# AD9854_V2_1.net
KiCad netlist of a schematic drawn in Altium Designer
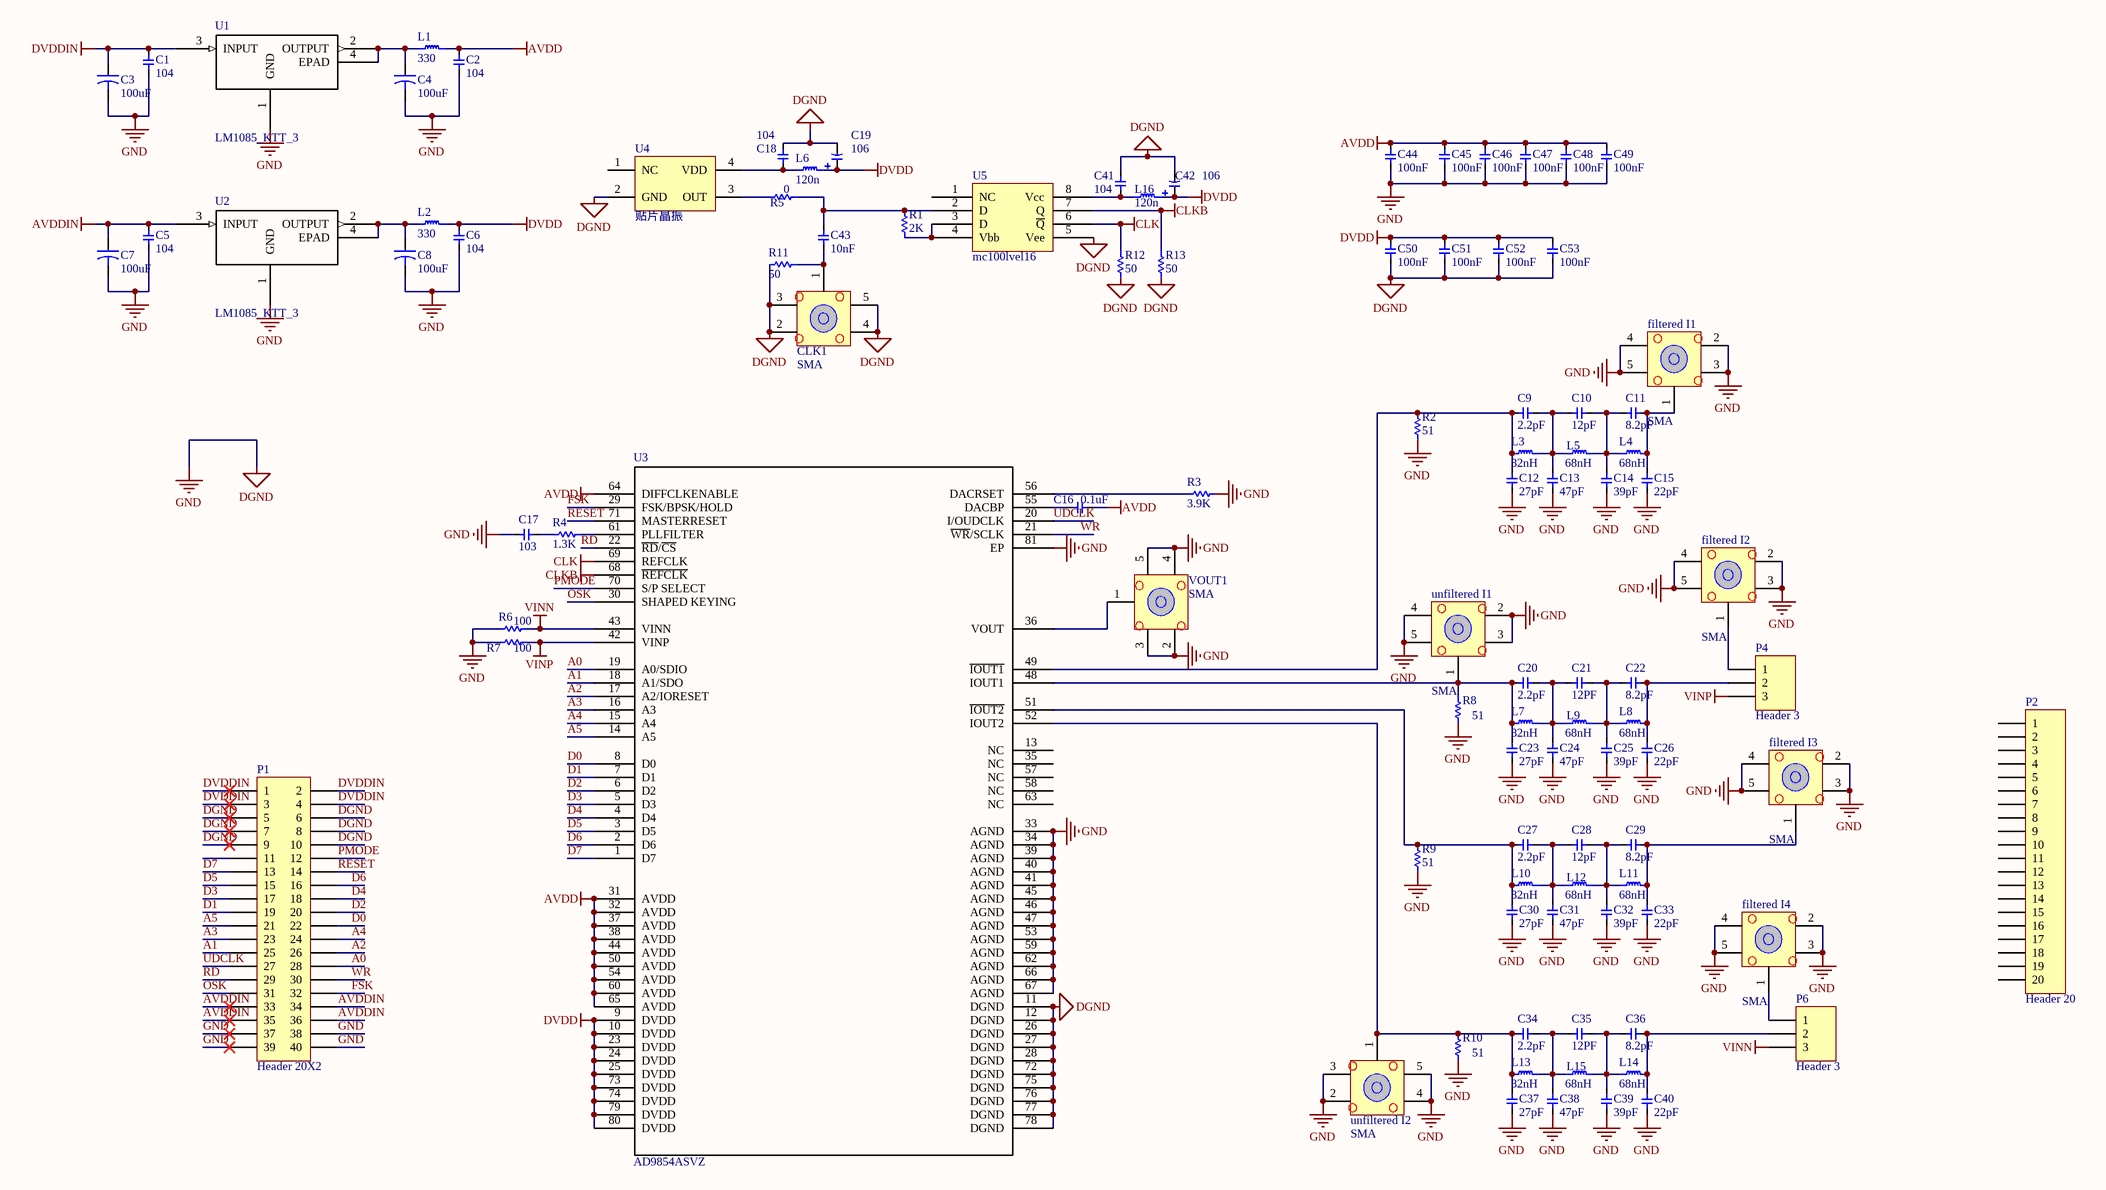
[diagram p0: AD9854_V2.1.SchDoc]

(export (version "E")
  (design (tool "Eeschema 10.0.6"))
  (components
    (comp (ref "C1")
      (value "104")
      (footprint "0805")
      (description "Capacitor")
      (fields (field (name "Comment") "Cap") (field (name "PUBLISHER") "Altium Limited"))
      (libsource (lib "Basic devices") (part "Cap"))
    )
    (comp (ref "C2")
      (value "104")
      (footprint "0805")
      (description "Capacitor")
      (fields (field (name "Comment") "Cap") (field (name "PUBLISHER") "Altium Limited"))
      (libsource (lib "Basic devices") (part "Cap"))
    )
    (comp (ref "C3")
      (value "100uF")
      (footprint "CAPR5-4X5")
      (description "Capacitor")
      (fields (field (name "Comment") "Cap2") (field (name "PUBLISHER") "Altium Limited"))
      (libsource (lib "Miscellaneous Devices") (part "Cap2"))
    )
    (comp (ref "C4")
      (value "100uF")
      (footprint "CAPR5-4X5")
      (description "Capacitor")
      (fields (field (name "Comment") "Cap2") (field (name "PUBLISHER") "Altium Limited"))
      (libsource (lib "Miscellaneous Devices") (part "Cap2"))
    )
    (comp (ref "C5")
      (value "104")
      (footprint "0805")
      (description "Capacitor")
      (fields (field (name "Comment") "Cap") (field (name "PUBLISHER") "Altium Limited"))
      (libsource (lib "Basic devices") (part "Cap"))
    )
    (comp (ref "C6")
      (value "104")
      (footprint "0805")
      (description "Capacitor")
      (fields (field (name "Comment") "Cap") (field (name "PUBLISHER") "Altium Limited"))
      (libsource (lib "Basic devices") (part "Cap"))
    )
    (comp (ref "C7")
      (value "100uF")
      (footprint "CAPR5-4X5")
      (description "Capacitor")
      (fields (field (name "Comment") "Cap2") (field (name "PUBLISHER") "Altium Limited"))
      (libsource (lib "Miscellaneous Devices") (part "Cap2"))
    )
    (comp (ref "C8")
      (value "100uF")
      (footprint "CAPR5-4X5")
      (description "Capacitor")
      (fields (field (name "Comment") "Cap2") (field (name "PUBLISHER") "Altium Limited"))
      (libsource (lib "Miscellaneous Devices") (part "Cap2"))
    )
    (comp (ref "C9")
      (value "2.2pF")
      (footprint "0805")
      (description "Capacitor")
      (fields (field (name "Comment") "Cap") (field (name "PUBLISHER") "Altium Limited"))
      (libsource (lib "Basic devices") (part "Cap"))
    )
    (comp (ref "C10")
      (value "12pF")
      (footprint "0805")
      (description "Capacitor")
      (fields (field (name "Comment") "Cap") (field (name "PUBLISHER") "Altium Limited"))
      (libsource (lib "Basic devices") (part "Cap"))
    )
    (comp (ref "C11")
      (value "8.2pF")
      (footprint "0805")
      (description "Capacitor")
      (fields (field (name "Comment") "Cap") (field (name "PUBLISHER") "Altium Limited"))
      (libsource (lib "Basic devices") (part "Cap"))
    )
    (comp (ref "C12")
      (value "27pF")
      (footprint "0805")
      (description "Capacitor")
      (fields (field (name "Comment") "Cap") (field (name "PUBLISHER") "Altium Limited"))
      (libsource (lib "Basic devices") (part "Cap"))
    )
    (comp (ref "C13")
      (value "47pF")
      (footprint "0805")
      (description "Capacitor")
      (fields (field (name "Comment") "Cap") (field (name "PUBLISHER") "Altium Limited"))
      (libsource (lib "Basic devices") (part "Cap"))
    )
    (comp (ref "C14")
      (value "39pF")
      (footprint "0805")
      (description "Capacitor")
      (fields (field (name "Comment") "Cap") (field (name "PUBLISHER") "Altium Limited"))
      (libsource (lib "Basic devices") (part "Cap"))
    )
    (comp (ref "C15")
      (value "22pF")
      (footprint "0805")
      (description "Capacitor")
      (fields (field (name "Comment") "Cap") (field (name "PUBLISHER") "Altium Limited"))
      (libsource (lib "Basic devices") (part "Cap"))
    )
    (comp (ref "C16")
      (value "0.1uF")
      (footprint "0805")
      (description "Capacitor")
      (fields (field (name "Comment") "Cap") (field (name "PUBLISHER") "Altium Limited"))
      (libsource (lib "Basic devices") (part "Cap"))
    )
    (comp (ref "C17")
      (value "103")
      (footprint "0805")
      (description "Capacitor")
      (fields (field (name "Comment") "Cap") (field (name "PUBLISHER") "Altium Limited"))
      (libsource (lib "Basic devices") (part "Cap"))
    )
    (comp (ref "C18")
      (value "104")
      (footprint "0805")
      (description "Capacitor")
      (fields (field (name "Comment") "Cap") (field (name "PUBLISHER") "Altium Limited"))
      (libsource (lib "Basic devices") (part "Cap"))
    )
    (comp (ref "C19")
      (value "106")
      (footprint "c1206 - duplicate")
      (description "Polarized Capacitor (Axial)")
      (fields (field (name "Comment") "Cap Pol") (field (name "PUBLISHER") "Altium Limited"))
      (libsource (lib "Basic devices") (part "Cap Pol"))
    )
    (comp (ref "C20")
      (value "2.2pF")
      (footprint "0805")
      (description "Capacitor")
      (fields (field (name "Comment") "Cap") (field (name "PUBLISHER") "Altium Limited"))
      (libsource (lib "Basic devices") (part "Cap"))
    )
    (comp (ref "C21")
      (value "12PF")
      (footprint "0805")
      (description "Capacitor")
      (fields (field (name "Comment") "Cap") (field (name "PUBLISHER") "Altium Limited"))
      (libsource (lib "Basic devices") (part "Cap"))
    )
    (comp (ref "C22")
      (value "8.2pF")
      (footprint "0805")
      (description "Capacitor")
      (fields (field (name "Comment") "Cap") (field (name "PUBLISHER") "Altium Limited"))
      (libsource (lib "Basic devices") (part "Cap"))
    )
    (comp (ref "C23")
      (value "27pF")
      (footprint "0805")
      (description "Capacitor")
      (fields (field (name "Comment") "Cap") (field (name "PUBLISHER") "Altium Limited"))
      (libsource (lib "Basic devices") (part "Cap"))
    )
    (comp (ref "C24")
      (value "47pF")
      (footprint "0805")
      (description "Capacitor")
      (fields (field (name "Comment") "Cap") (field (name "PUBLISHER") "Altium Limited"))
      (libsource (lib "Basic devices") (part "Cap"))
    )
    (comp (ref "C25")
      (value "39pF")
      (footprint "0805")
      (description "Capacitor")
      (fields (field (name "Comment") "Cap") (field (name "PUBLISHER") "Altium Limited"))
      (libsource (lib "Basic devices") (part "Cap"))
    )
    (comp (ref "C26")
      (value "22pF")
      (footprint "0805")
      (description "Capacitor")
      (fields (field (name "Comment") "Cap") (field (name "PUBLISHER") "Altium Limited"))
      (libsource (lib "Basic devices") (part "Cap"))
    )
    (comp (ref "C27")
      (value "2.2pF")
      (footprint "0805")
      (description "Capacitor")
      (fields (field (name "Comment") "Cap") (field (name "PUBLISHER") "Altium Limited"))
      (libsource (lib "Basic devices") (part "Cap"))
    )
    (comp (ref "C28")
      (value "12pF")
      (footprint "0805")
      (description "Capacitor")
      (fields (field (name "Comment") "Cap") (field (name "PUBLISHER") "Altium Limited"))
      (libsource (lib "Basic devices") (part "Cap"))
    )
    (comp (ref "C29")
      (value "8.2pF")
      (footprint "0805")
      (description "Capacitor")
      (fields (field (name "Comment") "Cap") (field (name "PUBLISHER") "Altium Limited"))
      (libsource (lib "Basic devices") (part "Cap"))
    )
    (comp (ref "C30")
      (value "27pF")
      (footprint "0805")
      (description "Capacitor")
      (fields (field (name "Comment") "Cap") (field (name "PUBLISHER") "Altium Limited"))
      (libsource (lib "Basic devices") (part "Cap"))
    )
    (comp (ref "C31")
      (value "47pF")
      (footprint "0805")
      (description "Capacitor")
      (fields (field (name "Comment") "Cap") (field (name "PUBLISHER") "Altium Limited"))
      (libsource (lib "Basic devices") (part "Cap"))
    )
    (comp (ref "C32")
      (value "39pF")
      (footprint "0805")
      (description "Capacitor")
      (fields (field (name "Comment") "Cap") (field (name "PUBLISHER") "Altium Limited"))
      (libsource (lib "Basic devices") (part "Cap"))
    )
    (comp (ref "C33")
      (value "22pF")
      (footprint "0805")
      (description "Capacitor")
      (fields (field (name "Comment") "Cap") (field (name "PUBLISHER") "Altium Limited"))
      (libsource (lib "Basic devices") (part "Cap"))
    )
    (comp (ref "C34")
      (value "2.2pF")
      (footprint "0805")
      (description "Capacitor")
      (fields (field (name "Comment") "Cap") (field (name "PUBLISHER") "Altium Limited"))
      (libsource (lib "Basic devices") (part "Cap"))
    )
    (comp (ref "C35")
      (value "12PF")
      (footprint "0805")
      (description "Capacitor")
      (fields (field (name "Comment") "Cap") (field (name "PUBLISHER") "Altium Limited"))
      (libsource (lib "Basic devices") (part "Cap"))
    )
    (comp (ref "C36")
      (value "8.2pF")
      (footprint "0805")
      (description "Capacitor")
      (fields (field (name "Comment") "Cap") (field (name "PUBLISHER") "Altium Limited"))
      (libsource (lib "Basic devices") (part "Cap"))
    )
    (comp (ref "C37")
      (value "27pF")
      (footprint "0805")
      (description "Capacitor")
      (fields (field (name "Comment") "Cap") (field (name "PUBLISHER") "Altium Limited"))
      (libsource (lib "Basic devices") (part "Cap"))
    )
    (comp (ref "C38")
      (value "47pF")
      (footprint "0805")
      (description "Capacitor")
      (fields (field (name "Comment") "Cap") (field (name "PUBLISHER") "Altium Limited"))
      (libsource (lib "Basic devices") (part "Cap"))
    )
    (comp (ref "C39")
      (value "39pF")
      (footprint "0805")
      (description "Capacitor")
      (fields (field (name "Comment") "Cap") (field (name "PUBLISHER") "Altium Limited"))
      (libsource (lib "Basic devices") (part "Cap"))
    )
    (comp (ref "C40")
      (value "22pF")
      (footprint "0805")
      (description "Capacitor")
      (fields (field (name "Comment") "Cap") (field (name "PUBLISHER") "Altium Limited"))
      (libsource (lib "Basic devices") (part "Cap"))
    )
    (comp (ref "C41")
      (value "104")
      (footprint "0805")
      (description "Capacitor")
      (fields (field (name "Comment") "Cap") (field (name "PUBLISHER") "Altium Limited"))
      (libsource (lib "Basic devices") (part "Cap"))
    )
    (comp (ref "C42")
      (value "106")
      (footprint "c1206 - duplicate")
      (description "Polarized Capacitor (Axial)")
      (fields (field (name "Comment") "Cap Pol") (field (name "PUBLISHER") "Altium Limited"))
      (libsource (lib "Basic devices") (part "Cap Pol"))
    )
    (comp (ref "C43")
      (value "10nF")
      (footprint "0805")
      (description "Capacitor")
      (fields (field (name "Comment") "Cap") (field (name "PUBLISHER") "Altium Limited"))
      (libsource (lib "Basic devices") (part "Cap"))
    )
    (comp (ref "C44")
      (value "100nF")
      (footprint "0805")
      (description "Capacitor")
      (fields (field (name "Comment") "Cap") (field (name "PUBLISHER") "Altium Limited"))
      (libsource (lib "Basic devices") (part "Cap"))
    )
    (comp (ref "C45")
      (value "100nF")
      (footprint "0805")
      (description "Capacitor")
      (fields (field (name "Comment") "Cap") (field (name "PUBLISHER") "Altium Limited"))
      (libsource (lib "Basic devices") (part "Cap"))
    )
    (comp (ref "C46")
      (value "100nF")
      (footprint "0805")
      (description "Capacitor")
      (fields (field (name "Comment") "Cap") (field (name "PUBLISHER") "Altium Limited"))
      (libsource (lib "Basic devices") (part "Cap"))
    )
    (comp (ref "C47")
      (value "100nF")
      (footprint "0805")
      (description "Capacitor")
      (fields (field (name "Comment") "Cap") (field (name "PUBLISHER") "Altium Limited"))
      (libsource (lib "Basic devices") (part "Cap"))
    )
    (comp (ref "C48")
      (value "100nF")
      (footprint "0805")
      (description "Capacitor")
      (fields (field (name "Comment") "Cap") (field (name "PUBLISHER") "Altium Limited"))
      (libsource (lib "Basic devices") (part "Cap"))
    )
    (comp (ref "C49")
      (value "100nF")
      (footprint "0805")
      (description "Capacitor")
      (fields (field (name "Comment") "Cap") (field (name "PUBLISHER") "Altium Limited"))
      (libsource (lib "Basic devices") (part "Cap"))
    )
    (comp (ref "C50")
      (value "100nF")
      (footprint "0805")
      (description "Capacitor")
      (fields (field (name "Comment") "Cap") (field (name "PUBLISHER") "Altium Limited"))
      (libsource (lib "Basic devices") (part "Cap"))
    )
    (comp (ref "C51")
      (value "100nF")
      (footprint "0805")
      (description "Capacitor")
      (fields (field (name "Comment") "Cap") (field (name "PUBLISHER") "Altium Limited"))
      (libsource (lib "Basic devices") (part "Cap"))
    )
    (comp (ref "C52")
      (value "100nF")
      (footprint "0805")
      (description "Capacitor")
      (fields (field (name "Comment") "Cap") (field (name "PUBLISHER") "Altium Limited"))
      (libsource (lib "Basic devices") (part "Cap"))
    )
    (comp (ref "C53")
      (value "100nF")
      (footprint "0805")
      (description "Capacitor")
      (fields (field (name "Comment") "Cap") (field (name "PUBLISHER") "Altium Limited"))
      (libsource (lib "Basic devices") (part "Cap"))
    )
    (comp (ref "CLK1") (value "SMA") (footprint "SMA") (libsource (lib "Z_Z20090825") (part "SMA")))
    (comp (ref "filtered I1") (value "SMA") (footprint "SMA") (libsource (lib "") (part "SMA_1")))
    (comp (ref "filtered I2") (value "SMA") (footprint "SMA") (libsource (lib "") (part "SMA_1")))
    (comp (ref "filtered I3") (value "SMA") (footprint "SMA") (libsource (lib "") (part "SMA_1")))
    (comp (ref "filtered I4") (value "SMA") (footprint "SMA") (libsource (lib "") (part "SMA_1")))
    (comp (ref "L1")
      (value "330")
      (footprint "INDP6055X45N")
      (description "Resistor")
      (fields (field (name "Comment") "ind") (field (name "PUBLISHER") "Altium Limited"))
      (libsource (lib "Basic devices") (part "ind"))
    )
    (comp (ref "L2")
      (value "330")
      (footprint "INDP6055X45N")
      (description "Resistor")
      (fields (field (name "Comment") "ind") (field (name "PUBLISHER") "Altium Limited"))
      (libsource (lib "Basic devices") (part "ind"))
    )
    (comp (ref "L3")
      (value "82nH")
      (footprint "0805")
      (description "Resistor")
      (fields (field (name "Comment") "ind") (field (name "PUBLISHER") "Altium Limited"))
      (libsource (lib "Basic devices") (part "ind"))
    )
    (comp (ref "L4")
      (value "68nH")
      (footprint "0805")
      (description "Resistor")
      (fields (field (name "Comment") "ind") (field (name "PUBLISHER") "Altium Limited"))
      (libsource (lib "Basic devices") (part "ind"))
    )
    (comp (ref "L5")
      (value "68nH")
      (footprint "0805")
      (description "Resistor")
      (fields (field (name "Comment") "ind") (field (name "PUBLISHER") "Altium Limited"))
      (libsource (lib "Basic devices") (part "ind"))
    )
    (comp (ref "L6")
      (value "120n")
      (footprint "0805")
      (description "Resistor")
      (fields (field (name "Comment") "ind") (field (name "PUBLISHER") "Altium Limited"))
      (libsource (lib "Basic devices") (part "ind"))
    )
    (comp (ref "L7")
      (value "82nH")
      (footprint "0805")
      (description "Resistor")
      (fields (field (name "Comment") "ind") (field (name "PUBLISHER") "Altium Limited"))
      (libsource (lib "Basic devices") (part "ind"))
    )
    (comp (ref "L8")
      (value "68nH")
      (footprint "0805")
      (description "Resistor")
      (fields (field (name "Comment") "ind") (field (name "PUBLISHER") "Altium Limited"))
      (libsource (lib "Basic devices") (part "ind"))
    )
    (comp (ref "L9")
      (value "68nH")
      (footprint "0805")
      (description "Resistor")
      (fields (field (name "Comment") "ind") (field (name "PUBLISHER") "Altium Limited"))
      (libsource (lib "Basic devices") (part "ind"))
    )
    (comp (ref "L10")
      (value "82nH")
      (footprint "0805")
      (description "Resistor")
      (fields (field (name "Comment") "ind") (field (name "PUBLISHER") "Altium Limited"))
      (libsource (lib "Basic devices") (part "ind"))
    )
    (comp (ref "L11")
      (value "68nH")
      (footprint "0805")
      (description "Resistor")
      (fields (field (name "Comment") "ind") (field (name "PUBLISHER") "Altium Limited"))
      (libsource (lib "Basic devices") (part "ind"))
    )
    (comp (ref "L12")
      (value "68nH")
      (footprint "0805")
      (description "Resistor")
      (fields (field (name "Comment") "ind") (field (name "PUBLISHER") "Altium Limited"))
      (libsource (lib "Basic devices") (part "ind"))
    )
    (comp (ref "L13")
      (value "82nH")
      (footprint "0805")
      (description "Resistor")
      (fields (field (name "Comment") "ind") (field (name "PUBLISHER") "Altium Limited"))
      (libsource (lib "Basic devices") (part "ind"))
    )
    (comp (ref "L14")
      (value "68nH")
      (footprint "0805")
      (description "Resistor")
      (fields (field (name "Comment") "ind") (field (name "PUBLISHER") "Altium Limited"))
      (libsource (lib "Basic devices") (part "ind"))
    )
    (comp (ref "L15")
      (value "68nH")
      (footprint "0805")
      (description "Resistor")
      (fields (field (name "Comment") "ind") (field (name "PUBLISHER") "Altium Limited"))
      (libsource (lib "Basic devices") (part "ind"))
    )
    (comp (ref "L16")
      (value "120n")
      (footprint "0805")
      (description "Resistor")
      (fields (field (name "Comment") "ind") (field (name "PUBLISHER") "Altium Limited"))
      (libsource (lib "Basic devices") (part "ind"))
    )
    (comp (ref "P1")
      (value "Header 20X2")
      (footprint "HDR2X20")
      (description "Header, 20-Pin, Dual row")
      (fields (field (name "PUBLISHER") "Altium Limited"))
      (libsource (lib "Miscellaneous Connectors") (part "Header 20X2"))
    )
    (comp (ref "P2")
      (value "Header 20")
      (footprint "HDR1X20")
      (description "Header, 20-Pin")
      (fields (field (name "PUBLISHER") "Altium Limited"))
      (libsource (lib "Miscellaneous Connectors") (part "Header 20"))
    )
    (comp (ref "P4")
      (value "Header 3")
      (footprint "HDR1X3")
      (description "Header, 3-Pin")
      (fields (field (name "PUBLISHER") "Altium Limited"))
      (libsource (lib "Miscellaneous Connectors") (part "Header 3"))
    )
    (comp (ref "P6")
      (value "Header 3")
      (footprint "HDR1X3")
      (description "Header, 3-Pin")
      (fields (field (name "PUBLISHER") "Altium Limited"))
      (libsource (lib "Miscellaneous Connectors") (part "Header 3"))
    )
    (comp (ref "R1")
      (value "2K")
      (footprint "0805")
      (description "Resistor")
      (fields (field (name "Comment") "Res") (field (name "PUBLISHER") "Altium Limited"))
      (libsource (lib "Basic devices") (part "Res"))
    )
    (comp (ref "R2")
      (value "51")
      (footprint "0805")
      (description "Resistor")
      (fields (field (name "Comment") "Res") (field (name "PUBLISHER") "Altium Limited"))
      (libsource (lib "Basic devices") (part "Res"))
    )
    (comp (ref "R3")
      (value "3.9K")
      (footprint "0805")
      (description "Resistor")
      (fields (field (name "Comment") "Res") (field (name "PUBLISHER") "Altium Limited"))
      (libsource (lib "Basic devices") (part "Res"))
    )
    (comp (ref "R4")
      (value "1.3K")
      (footprint "0805")
      (description "Resistor")
      (fields (field (name "Comment") "Res") (field (name "PUBLISHER") "Altium Limited"))
      (libsource (lib "Basic devices") (part "Res"))
    )
    (comp (ref "R5")
      (value "0")
      (footprint "0805")
      (description "Resistor")
      (fields (field (name "Comment") "Res") (field (name "PUBLISHER") "Altium Limited"))
      (libsource (lib "Basic devices") (part "Res"))
    )
    (comp (ref "R6")
      (value "100")
      (footprint "0805")
      (description "Resistor")
      (fields (field (name "Comment") "Res") (field (name "PUBLISHER") "Altium Limited"))
      (libsource (lib "Basic devices") (part "Res"))
    )
    (comp (ref "R7")
      (value "100")
      (footprint "0805")
      (description "Resistor")
      (fields (field (name "Comment") "Res") (field (name "PUBLISHER") "Altium Limited"))
      (libsource (lib "Basic devices") (part "Res"))
    )
    (comp (ref "R8")
      (value "51")
      (footprint "0805")
      (description "Resistor")
      (fields (field (name "Comment") "Res") (field (name "PUBLISHER") "Altium Limited"))
      (libsource (lib "Basic devices") (part "Res"))
    )
    (comp (ref "R9")
      (value "51")
      (footprint "0805")
      (description "Resistor")
      (fields (field (name "Comment") "Res") (field (name "PUBLISHER") "Altium Limited"))
      (libsource (lib "Basic devices") (part "Res"))
    )
    (comp (ref "R10")
      (value "51")
      (footprint "0805")
      (description "Resistor")
      (fields (field (name "Comment") "Res") (field (name "PUBLISHER") "Altium Limited"))
      (libsource (lib "Basic devices") (part "Res"))
    )
    (comp (ref "R11")
      (value "50")
      (footprint "0805")
      (description "Resistor")
      (fields (field (name "Comment") "Res") (field (name "PUBLISHER") "Altium Limited"))
      (libsource (lib "Basic devices") (part "Res"))
    )
    (comp (ref "R12")
      (value "50")
      (footprint "0805")
      (description "Resistor")
      (fields (field (name "Comment") "Res") (field (name "PUBLISHER") "Altium Limited"))
      (libsource (lib "Basic devices") (part "Res"))
    )
    (comp (ref "R13")
      (value "50")
      (footprint "0805")
      (description "Resistor")
      (fields (field (name "Comment") "Res") (field (name "PUBLISHER") "Altium Limited"))
      (libsource (lib "Basic devices") (part "Res"))
    )
    (comp (ref "U1")
      (value "LM1085_KTT_3")
      (footprint "KTT3-M")
      (description "Imported")
      (fields (field (name "MANUFACTURER_PART_NUMBER") "lm1085_ktt_3"))
      (libsource (lib "AD_DA") (part "LM1085_KTT_3"))
    )
    (comp (ref "U2")
      (value "LM1085_KTT_3")
      (footprint "KTT3-M")
      (description "Imported")
      (fields (field (name "MANUFACTURER_PART_NUMBER") "lm1085_ktt_3"))
      (libsource (lib "AD_DA") (part "LM1085_KTT_3"))
    )
    (comp (ref "U3")
      (value "AD9854ASVZ")
      (footprint "SV_80_4-M")
      (description "Imported")
      (libsource (lib "AD_DA") (part "AD9854ASVZ"))
    )
    (comp (ref "U4") (value "贴片晶振") (footprint "贴片晶振") (libsource (lib "AD_DA") (part "贴片晶振")))
    (comp (ref "U5") (value "mc100lvel16") (footprint "D8") (libsource (lib "AD_DA") (part "mc100lvel16")))
    (comp (ref "unfiltered I1") (value "SMA") (footprint "SMA") (libsource (lib "") (part "SMA_1")))
    (comp (ref "unfiltered I2") (value "SMA") (footprint "SMA") (libsource (lib "Z_Z20090825") (part "SMA")))
    (comp (ref "VOUT1") (value "SMA") (footprint "SMA") (libsource (lib "") (part "SMA_2")))
  )
  (nets
    (net (code "1") (name "/A0") (class "Default")
      (node (ref "P1") (pin "28") (pinfunction "28_28") (pintype "passive"))
      (node (ref "U3") (pin "19") (pinfunction "A0/SDIO_19") (pintype "passive"))
    )
    (net (code "2") (name "/A1") (class "Default")
      (node (ref "P1") (pin "25") (pinfunction "25_25") (pintype "passive"))
      (node (ref "U3") (pin "18") (pinfunction "A1/SDO_18") (pintype "passive"))
    )
    (net (code "3") (name "/A2") (class "Default")
      (node (ref "P1") (pin "26") (pinfunction "26_26") (pintype "passive"))
      (node (ref "U3") (pin "17") (pinfunction "A2/IORESET_17") (pintype "passive"))
    )
    (net (code "4") (name "/A3") (class "Default")
      (node (ref "P1") (pin "23") (pinfunction "23_23") (pintype "passive"))
      (node (ref "U3") (pin "16") (pinfunction "A3_16") (pintype "passive"))
    )
    (net (code "5") (name "/A4") (class "Default")
      (node (ref "P1") (pin "24") (pinfunction "24_24") (pintype "passive"))
      (node (ref "U3") (pin "15") (pinfunction "A4_15") (pintype "passive"))
    )
    (net (code "6") (name "/A5") (class "Default")
      (node (ref "P1") (pin "21") (pinfunction "21_21") (pintype "passive"))
      (node (ref "U3") (pin "14") (pinfunction "A5_14") (pintype "passive"))
    )
    (net (code "7") (name "/D0") (class "Default")
      (node (ref "P1") (pin "22") (pinfunction "22_22") (pintype "passive"))
      (node (ref "U3") (pin "8") (pinfunction "D0_8") (pintype "passive"))
    )
    (net (code "8") (name "/D1") (class "Default")
      (node (ref "P1") (pin "19") (pinfunction "19_19") (pintype "passive"))
      (node (ref "U3") (pin "7") (pinfunction "D1_7") (pintype "passive"))
    )
    (net (code "9") (name "/D2") (class "Default")
      (node (ref "P1") (pin "20") (pinfunction "20_20") (pintype "passive"))
      (node (ref "U3") (pin "6") (pinfunction "D2_6") (pintype "passive"))
    )
    (net (code "10") (name "/D3") (class "Default")
      (node (ref "P1") (pin "17") (pinfunction "17_17") (pintype "passive"))
      (node (ref "U3") (pin "5") (pinfunction "D3_5") (pintype "passive"))
    )
    (net (code "11") (name "/D4") (class "Default")
      (node (ref "P1") (pin "18") (pinfunction "18_18") (pintype "passive"))
      (node (ref "U3") (pin "4") (pinfunction "D4_4") (pintype "passive"))
    )
    (net (code "12") (name "/D5") (class "Default")
      (node (ref "P1") (pin "15") (pinfunction "15_15") (pintype "passive"))
      (node (ref "U3") (pin "3") (pinfunction "D5_3") (pintype "passive"))
    )
    (net (code "13") (name "/D6") (class "Default")
      (node (ref "P1") (pin "16") (pinfunction "16_16") (pintype "passive"))
      (node (ref "U3") (pin "2") (pinfunction "D6_2") (pintype "passive"))
    )
    (net (code "14") (name "/D7") (class "Default")
      (node (ref "P1") (pin "13") (pinfunction "13_13") (pintype "passive"))
      (node (ref "U3") (pin "1") (pinfunction "D7_1") (pintype "passive"))
    )
    (net (code "15") (name "/FSK") (class "Default")
      (node (ref "P1") (pin "32") (pinfunction "32_32") (pintype "passive"))
      (node (ref "U3") (pin "29") (pinfunction "FSK/BPSK/HOLD_29") (pintype "passive"))
    )
    (net (code "16") (name "/OSK") (class "Default")
      (node (ref "P1") (pin "31") (pinfunction "31_31") (pintype "passive"))
      (node (ref "U3") (pin "30") (pinfunction "SHAPED_KEYING_30") (pintype "passive"))
    )
    (net (code "17") (name "/PMODE") (class "Default")
      (node (ref "P1") (pin "12") (pinfunction "12_12") (pintype "passive"))
      (node (ref "U3") (pin "70") (pinfunction "S/P_SELECT_70") (pintype "passive"))
    )
    (net (code "18") (name "/RD") (class "Default")
      (node (ref "P1") (pin "29") (pinfunction "29_29") (pintype "passive"))
      (node (ref "U3") (pin "22") (pinfunction "~{RD}/~{CS}_22") (pintype "passive"))
    )
    (net (code "19") (name "/RESET") (class "Default")
      (node (ref "P1") (pin "14") (pinfunction "14_14") (pintype "passive"))
      (node (ref "U3") (pin "71") (pinfunction "MASTERRESET_71") (pintype "passive"))
    )
    (net (code "20") (name "/UDCLK") (class "Default")
      (node (ref "P1") (pin "27") (pinfunction "27_27") (pintype "passive"))
      (node (ref "U3") (pin "20") (pinfunction "I/OUDCLK_20") (pintype "passive"))
    )
    (net (code "21") (name "/WR") (class "Default")
      (node (ref "P1") (pin "30") (pinfunction "30_30") (pintype "passive"))
      (node (ref "U3") (pin "21") (pinfunction "~{WR}/SCLK_21") (pintype "passive"))
    )
    (net (code "22") (name "AVDD") (class "Default")
      (node (ref "C16") (pin "2") (pinfunction "2_2") (pintype "passive"))
      (node (ref "C2") (pin "1") (pinfunction "1_1") (pintype "passive"))
      (node (ref "C44") (pin "2") (pinfunction "2_2") (pintype "passive"))
      (node (ref "C45") (pin "2") (pinfunction "2_2") (pintype "passive"))
      (node (ref "C46") (pin "2") (pinfunction "2_2") (pintype "passive"))
      (node (ref "C47") (pin "2") (pinfunction "2_2") (pintype "passive"))
      (node (ref "C48") (pin "2") (pinfunction "2_2") (pintype "passive"))
      (node (ref "C49") (pin "2") (pinfunction "2_2") (pintype "passive"))
      (node (ref "L1") (pin "2") (pinfunction "2_2") (pintype "passive"))
      (node (ref "U3") (pin "31") (pinfunction "AVDD_31") (pintype "power_in"))
      (node (ref "U3") (pin "32") (pinfunction "AVDD_32") (pintype "power_in"))
      (node (ref "U3") (pin "37") (pinfunction "AVDD_37") (pintype "power_in"))
      (node (ref "U3") (pin "38") (pinfunction "AVDD_38") (pintype "power_in"))
      (node (ref "U3") (pin "44") (pinfunction "AVDD_44") (pintype "power_in"))
      (node (ref "U3") (pin "50") (pinfunction "AVDD_50") (pintype "power_in"))
      (node (ref "U3") (pin "54") (pinfunction "AVDD_54") (pintype "power_in"))
      (node (ref "U3") (pin "60") (pinfunction "AVDD_60") (pintype "power_in"))
      (node (ref "U3") (pin "64") (pinfunction "DIFFCLKENABLE_64") (pintype "passive"))
      (node (ref "U3") (pin "65") (pinfunction "AVDD_65") (pintype "power_in"))
    )
    (net (code "23") (name "AVDDIN") (class "Default")
      (node (ref "C5") (pin "1") (pinfunction "1_1") (pintype "passive"))
      (node (ref "C7") (pin "1") (pinfunction "1_1") (pintype "passive"))
      (node (ref "P1") (pin "33") (pinfunction "33_33") (pintype "passive"))
      (node (ref "P1") (pin "34") (pinfunction "34_34") (pintype "passive"))
      (node (ref "P1") (pin "35") (pinfunction "35_35") (pintype "passive"))
      (node (ref "P1") (pin "36") (pinfunction "36_36") (pintype "passive"))
      (node (ref "U2") (pin "3") (pinfunction "INPUT_3") (pintype "input"))
    )
    (net (code "24") (name "CLK") (class "Default")
      (node (ref "R12") (pin "2") (pinfunction "2_2") (pintype "passive"))
      (node (ref "U3") (pin "69") (pinfunction "REFCLK_69") (pintype "passive"))
      (node (ref "U5") (pin "6") (pinfunction "~{Q}_6") (pintype "passive"))
    )
    (net (code "25") (name "CLKB") (class "Default")
      (node (ref "R13") (pin "2") (pinfunction "2_2") (pintype "passive"))
      (node (ref "U3") (pin "68") (pinfunction "~{REFCLK}_68") (pintype "passive"))
      (node (ref "U5") (pin "7") (pinfunction "Q_7") (pintype "passive"))
    )
    (net (code "26") (name "DGND") (class "Default")
      (node (ref "C1") (pin "2") (pinfunction "2_2") (pintype "passive"))
      (node (ref "C12") (pin "1") (pinfunction "1_1") (pintype "passive"))
      (node (ref "C13") (pin "1") (pinfunction "1_1") (pintype "passive"))
      (node (ref "C14") (pin "1") (pinfunction "1_1") (pintype "passive"))
      (node (ref "C15") (pin "1") (pinfunction "1_1") (pintype "passive"))
      (node (ref "C17") (pin "2") (pinfunction "2_2") (pintype "passive"))
      (node (ref "C18") (pin "2") (pinfunction "2_2") (pintype "passive"))
      (node (ref "C19") (pin "2") (pinfunction "2_2") (pintype "passive"))
      (node (ref "C2") (pin "2") (pinfunction "2_2") (pintype "passive"))
      (node (ref "C23") (pin "1") (pinfunction "1_1") (pintype "passive"))
      (node (ref "C24") (pin "1") (pinfunction "1_1") (pintype "passive"))
      (node (ref "C25") (pin "1") (pinfunction "1_1") (pintype "passive"))
      (node (ref "C26") (pin "1") (pinfunction "1_1") (pintype "passive"))
      (node (ref "C3") (pin "2") (pinfunction "2_2") (pintype "passive"))
      (node (ref "C30") (pin "1") (pinfunction "1_1") (pintype "passive"))
      (node (ref "C31") (pin "1") (pinfunction "1_1") (pintype "passive"))
      (node (ref "C32") (pin "1") (pinfunction "1_1") (pintype "passive"))
      (node (ref "C33") (pin "1") (pinfunction "1_1") (pintype "passive"))
      (node (ref "C37") (pin "1") (pinfunction "1_1") (pintype "passive"))
      (node (ref "C38") (pin "1") (pinfunction "1_1") (pintype "passive"))
      (node (ref "C39") (pin "1") (pinfunction "1_1") (pintype "passive"))
      (node (ref "C4") (pin "2") (pinfunction "2_2") (pintype "passive"))
      (node (ref "C40") (pin "1") (pinfunction "1_1") (pintype "passive"))
      (node (ref "C41") (pin "1") (pinfunction "1_1") (pintype "passive"))
      (node (ref "C42") (pin "2") (pinfunction "2_2") (pintype "passive"))
      (node (ref "C44") (pin "1") (pinfunction "1_1") (pintype "passive"))
      (node (ref "C45") (pin "1") (pinfunction "1_1") (pintype "passive"))
      (node (ref "C46") (pin "1") (pinfunction "1_1") (pintype "passive"))
      (node (ref "C47") (pin "1") (pinfunction "1_1") (pintype "passive"))
      (node (ref "C48") (pin "1") (pinfunction "1_1") (pintype "passive"))
      (node (ref "C49") (pin "1") (pinfunction "1_1") (pintype "passive"))
      (node (ref "C5") (pin "2") (pinfunction "2_2") (pintype "passive"))
      (node (ref "C50") (pin "1") (pinfunction "1_1") (pintype "passive"))
      (node (ref "C51") (pin "1") (pinfunction "1_1") (pintype "passive"))
      (node (ref "C52") (pin "1") (pinfunction "1_1") (pintype "passive"))
      (node (ref "C53") (pin "1") (pinfunction "1_1") (pintype "passive"))
      (node (ref "C6") (pin "2") (pinfunction "2_2") (pintype "passive"))
      (node (ref "C7") (pin "2") (pinfunction "2_2") (pintype "passive"))
      (node (ref "C8") (pin "2") (pinfunction "2_2") (pintype "passive"))
      (node (ref "CLK1") (pin "2") (pintype "passive"))
      (node (ref "CLK1") (pin "3") (pintype "passive"))
      (node (ref "CLK1") (pin "4") (pintype "passive"))
      (node (ref "CLK1") (pin "5") (pintype "passive"))
      (node (ref "P1") (pin "10") (pinfunction "10_10") (pintype "passive"))
      (node (ref "P1") (pin "37") (pinfunction "37_37") (pintype "passive"))
      (node (ref "P1") (pin "38") (pinfunction "38_38") (pintype "passive"))
      (node (ref "P1") (pin "39") (pinfunction "39_39") (pintype "passive"))
      (node (ref "P1") (pin "40") (pinfunction "40_40") (pintype "passive"))
      (node (ref "P1") (pin "5") (pinfunction "5_5") (pintype "passive"))
      (node (ref "P1") (pin "6") (pinfunction "6_6") (pintype "passive"))
      (node (ref "P1") (pin "7") (pinfunction "7_7") (pintype "passive"))
      (node (ref "P1") (pin "8") (pinfunction "8_8") (pintype "passive"))
      (node (ref "P1") (pin "9") (pinfunction "9_9") (pintype "passive"))
      (node (ref "R10") (pin "1") (pinfunction "1_1") (pintype "passive"))
      (node (ref "R11") (pin "1") (pinfunction "1_1") (pintype "passive"))
      (node (ref "R12") (pin "1") (pinfunction "1_1") (pintype "passive"))
      (node (ref "R13") (pin "1") (pinfunction "1_1") (pintype "passive"))
      (node (ref "R2") (pin "1") (pinfunction "1_1") (pintype "passive"))
      (node (ref "R3") (pin "2") (pinfunction "2_2") (pintype "passive"))
      (node (ref "R6") (pin "1") (pinfunction "1_1") (pintype "passive"))
      (node (ref "R7") (pin "1") (pinfunction "1_1") (pintype "passive"))
      (node (ref "R8") (pin "1") (pinfunction "1_1") (pintype "passive"))
      (node (ref "R9") (pin "1") (pinfunction "1_1") (pintype "passive"))
      (node (ref "U1") (pin "1") (pinfunction "GND_1") (pintype "passive"))
      (node (ref "U2") (pin "1") (pinfunction "GND_1") (pintype "passive"))
      (node (ref "U3") (pin "11") (pinfunction "DGND_11") (pintype "passive"))
      (node (ref "U3") (pin "12") (pinfunction "DGND_12") (pintype "passive"))
      (node (ref "U3") (pin "26") (pinfunction "DGND_26") (pintype "passive"))
      (node (ref "U3") (pin "27") (pinfunction "DGND_27") (pintype "passive"))
      (node (ref "U3") (pin "28") (pinfunction "DGND_28") (pintype "passive"))
      (node (ref "U3") (pin "33") (pinfunction "AGND_33") (pintype "passive"))
      (node (ref "U3") (pin "34") (pinfunction "AGND_34") (pintype "passive"))
      (node (ref "U3") (pin "39") (pinfunction "AGND_39") (pintype "passive"))
      (node (ref "U3") (pin "40") (pinfunction "AGND_40") (pintype "passive"))
      (node (ref "U3") (pin "41") (pinfunction "AGND_41") (pintype "passive"))
      (node (ref "U3") (pin "45") (pinfunction "AGND_45") (pintype "passive"))
      (node (ref "U3") (pin "46") (pinfunction "AGND_46") (pintype "passive"))
      (node (ref "U3") (pin "47") (pinfunction "AGND_47") (pintype "passive"))
      (node (ref "U3") (pin "53") (pinfunction "AGND_53") (pintype "passive"))
      (node (ref "U3") (pin "59") (pinfunction "AGND_59") (pintype "passive"))
      (node (ref "U3") (pin "62") (pinfunction "AGND_62") (pintype "passive"))
      (node (ref "U3") (pin "66") (pinfunction "AGND_66") (pintype "passive"))
      (node (ref "U3") (pin "67") (pinfunction "AGND_67") (pintype "passive"))
      (node (ref "U3") (pin "72") (pinfunction "DGND_72") (pintype "passive"))
      (node (ref "U3") (pin "75") (pinfunction "DGND_75") (pintype "passive"))
      (node (ref "U3") (pin "76") (pinfunction "DGND_76") (pintype "passive"))
      (node (ref "U3") (pin "77") (pinfunction "DGND_77") (pintype "passive"))
      (node (ref "U3") (pin "78") (pinfunction "DGND_78") (pintype "passive"))
      (node (ref "U3") (pin "81") (pinfunction "EP_81") (pintype "passive"))
      (node (ref "U4") (pin "2") (pinfunction "GND_2") (pintype "passive"))
      (node (ref "U5") (pin "5") (pinfunction "Vee_5") (pintype "passive"))
      (node (ref "VOUT1") (pin "2") (pintype "passive"))
      (node (ref "VOUT1") (pin "3") (pintype "passive"))
      (node (ref "VOUT1") (pin "4") (pintype "passive"))
      (node (ref "VOUT1") (pin "5") (pintype "passive"))
      (node (ref "filtered I1") (pin "2") (pintype "passive"))
      (node (ref "filtered I1") (pin "3") (pintype "passive"))
      (node (ref "filtered I1") (pin "4") (pintype "passive"))
      (node (ref "filtered I1") (pin "5") (pintype "passive"))
      (node (ref "filtered I2") (pin "2") (pintype "passive"))
      (node (ref "filtered I2") (pin "3") (pintype "passive"))
      (node (ref "filtered I2") (pin "4") (pintype "passive"))
      (node (ref "filtered I2") (pin "5") (pintype "passive"))
      (node (ref "filtered I3") (pin "2") (pintype "passive"))
      (node (ref "filtered I3") (pin "3") (pintype "passive"))
      (node (ref "filtered I3") (pin "4") (pintype "passive"))
      (node (ref "filtered I3") (pin "5") (pintype "passive"))
      (node (ref "filtered I4") (pin "2") (pintype "passive"))
      (node (ref "filtered I4") (pin "3") (pintype "passive"))
      (node (ref "filtered I4") (pin "4") (pintype "passive"))
      (node (ref "filtered I4") (pin "5") (pintype "passive"))
      (node (ref "unfiltered I1") (pin "2") (pintype "passive"))
      (node (ref "unfiltered I1") (pin "3") (pintype "passive"))
      (node (ref "unfiltered I1") (pin "4") (pintype "passive"))
      (node (ref "unfiltered I1") (pin "5") (pintype "passive"))
      (node (ref "unfiltered I2") (pin "2") (pintype "passive"))
      (node (ref "unfiltered I2") (pin "3") (pintype "passive"))
      (node (ref "unfiltered I2") (pin "4") (pintype "passive"))
      (node (ref "unfiltered I2") (pin "5") (pintype "passive"))
    )
    (net (code "27") (name "DVDD") (class "Default")
      (node (ref "C19") (pin "1") (pinfunction "1_1") (pintype "passive"))
      (node (ref "C42") (pin "1") (pinfunction "1_1") (pintype "passive"))
      (node (ref "C50") (pin "2") (pinfunction "2_2") (pintype "passive"))
      (node (ref "C51") (pin "2") (pinfunction "2_2") (pintype "passive"))
      (node (ref "C52") (pin "2") (pinfunction "2_2") (pintype "passive"))
      (node (ref "C53") (pin "2") (pinfunction "2_2") (pintype "passive"))
      (node (ref "C6") (pin "1") (pinfunction "1_1") (pintype "passive"))
      (node (ref "L16") (pin "2") (pinfunction "2_2") (pintype "passive"))
      (node (ref "L2") (pin "2") (pinfunction "2_2") (pintype "passive"))
      (node (ref "L6") (pin "2") (pinfunction "2_2") (pintype "passive"))
      (node (ref "U3") (pin "10") (pinfunction "DVDD_10") (pintype "power_in"))
      (node (ref "U3") (pin "23") (pinfunction "DVDD_23") (pintype "power_in"))
      (node (ref "U3") (pin "24") (pinfunction "DVDD_24") (pintype "power_in"))
      (node (ref "U3") (pin "25") (pinfunction "DVDD_25") (pintype "power_in"))
      (node (ref "U3") (pin "73") (pinfunction "DVDD_73") (pintype "power_in"))
      (node (ref "U3") (pin "74") (pinfunction "DVDD_74") (pintype "power_in"))
      (node (ref "U3") (pin "79") (pinfunction "DVDD_79") (pintype "power_in"))
      (node (ref "U3") (pin "80") (pinfunction "DVDD_80") (pintype "power_in"))
      (node (ref "U3") (pin "9") (pinfunction "DVDD_9") (pintype "power_in"))
    )
    (net (code "28") (name "DVDDIN") (class "Default")
      (node (ref "C1") (pin "1") (pinfunction "1_1") (pintype "passive"))
      (node (ref "C3") (pin "1") (pinfunction "1_1") (pintype "passive"))
      (node (ref "P1") (pin "1") (pinfunction "1_1") (pintype "passive"))
      (node (ref "P1") (pin "2") (pinfunction "2_2") (pintype "passive"))
      (node (ref "P1") (pin "3") (pinfunction "3_3") (pintype "passive"))
      (node (ref "P1") (pin "4") (pinfunction "4_4") (pintype "passive"))
      (node (ref "U1") (pin "3") (pinfunction "INPUT_3") (pintype "input"))
    )
    (net (code "29") (name "Net-(C10-Pad1)") (class "Default")
      (node (ref "C10") (pin "1") (pinfunction "1_1") (pintype "passive"))
      (node (ref "C13") (pin "2") (pinfunction "2_2") (pintype "passive"))
      (node (ref "C9") (pin "2") (pinfunction "2_2") (pintype "passive"))
      (node (ref "L3") (pin "2") (pinfunction "2_2") (pintype "passive"))
      (node (ref "L5") (pin "1") (pinfunction "1_1") (pintype "passive"))
    )
    (net (code "30") (name "Net-(C10-Pad2)") (class "Default")
      (node (ref "C10") (pin "2") (pinfunction "2_2") (pintype "passive"))
      (node (ref "C11") (pin "1") (pinfunction "1_1") (pintype "passive"))
      (node (ref "C14") (pin "2") (pinfunction "2_2") (pintype "passive"))
      (node (ref "L4") (pin "1") (pinfunction "1_1") (pintype "passive"))
      (node (ref "L5") (pin "2") (pinfunction "2_2") (pintype "passive"))
    )
    (net (code "31") (name "Net-(C11-Pad2)") (class "Default")
      (node (ref "C11") (pin "2") (pinfunction "2_2") (pintype "passive"))
      (node (ref "C15") (pin "2") (pinfunction "2_2") (pintype "passive"))
      (node (ref "L4") (pin "2") (pinfunction "2_2") (pintype "passive"))
      (node (ref "filtered I1") (pin "1") (pintype "passive"))
    )
    (net (code "32") (name "Net-(C17-Pad1)") (class "Default")
      (node (ref "C17") (pin "1") (pinfunction "1_1") (pintype "passive"))
      (node (ref "R4") (pin "2") (pinfunction "2_2") (pintype "passive"))
    )
    (net (code "33") (name "Net-(C20-Pad2)") (class "Default")
      (node (ref "C20") (pin "2") (pinfunction "2_2") (pintype "passive"))
      (node (ref "C21") (pin "1") (pinfunction "1_1") (pintype "passive"))
      (node (ref "C24") (pin "2") (pinfunction "2_2") (pintype "passive"))
      (node (ref "L7") (pin "2") (pinfunction "2_2") (pintype "passive"))
      (node (ref "L9") (pin "1") (pinfunction "1_1") (pintype "passive"))
    )
    (net (code "34") (name "Net-(C21-Pad2)") (class "Default")
      (node (ref "C21") (pin "2") (pinfunction "2_2") (pintype "passive"))
      (node (ref "C22") (pin "1") (pinfunction "1_1") (pintype "passive"))
      (node (ref "C25") (pin "2") (pinfunction "2_2") (pintype "passive"))
      (node (ref "L8") (pin "1") (pinfunction "1_1") (pintype "passive"))
      (node (ref "L9") (pin "2") (pinfunction "2_2") (pintype "passive"))
    )
    (net (code "35") (name "Net-(C22-Pad2)") (class "Default")
      (node (ref "C22") (pin "2") (pinfunction "2_2") (pintype "passive"))
      (node (ref "C26") (pin "2") (pinfunction "2_2") (pintype "passive"))
      (node (ref "L8") (pin "2") (pinfunction "2_2") (pintype "passive"))
      (node (ref "P4") (pin "2") (pinfunction "2_2") (pintype "passive"))
    )
    (net (code "36") (name "Net-(C27-Pad2)") (class "Default")
      (node (ref "C27") (pin "2") (pinfunction "2_2") (pintype "passive"))
      (node (ref "C28") (pin "1") (pinfunction "1_1") (pintype "passive"))
      (node (ref "C31") (pin "2") (pinfunction "2_2") (pintype "passive"))
      (node (ref "L10") (pin "2") (pinfunction "2_2") (pintype "passive"))
      (node (ref "L12") (pin "1") (pinfunction "1_1") (pintype "passive"))
    )
    (net (code "37") (name "Net-(C28-Pad2)") (class "Default")
      (node (ref "C28") (pin "2") (pinfunction "2_2") (pintype "passive"))
      (node (ref "C29") (pin "1") (pinfunction "1_1") (pintype "passive"))
      (node (ref "C32") (pin "2") (pinfunction "2_2") (pintype "passive"))
      (node (ref "L11") (pin "1") (pinfunction "1_1") (pintype "passive"))
      (node (ref "L12") (pin "2") (pinfunction "2_2") (pintype "passive"))
    )
    (net (code "38") (name "Net-(C29-Pad2)") (class "Default")
      (node (ref "C29") (pin "2") (pinfunction "2_2") (pintype "passive"))
      (node (ref "C33") (pin "2") (pinfunction "2_2") (pintype "passive"))
      (node (ref "L11") (pin "2") (pinfunction "2_2") (pintype "passive"))
      (node (ref "filtered I3") (pin "1") (pintype "passive"))
    )
    (net (code "39") (name "Net-(C34-Pad2)") (class "Default")
      (node (ref "C34") (pin "2") (pinfunction "2_2") (pintype "passive"))
      (node (ref "C35") (pin "1") (pinfunction "1_1") (pintype "passive"))
      (node (ref "C38") (pin "2") (pinfunction "2_2") (pintype "passive"))
      (node (ref "L13") (pin "2") (pinfunction "2_2") (pintype "passive"))
      (node (ref "L15") (pin "1") (pinfunction "1_1") (pintype "passive"))
    )
    (net (code "40") (name "Net-(C35-Pad2)") (class "Default")
      (node (ref "C35") (pin "2") (pinfunction "2_2") (pintype "passive"))
      (node (ref "C36") (pin "1") (pinfunction "1_1") (pintype "passive"))
      (node (ref "C39") (pin "2") (pinfunction "2_2") (pintype "passive"))
      (node (ref "L14") (pin "1") (pinfunction "1_1") (pintype "passive"))
      (node (ref "L15") (pin "2") (pinfunction "2_2") (pintype "passive"))
    )
    (net (code "41") (name "Net-(C36-Pad2)") (class "Default")
      (node (ref "C36") (pin "2") (pinfunction "2_2") (pintype "passive"))
      (node (ref "C40") (pin "2") (pinfunction "2_2") (pintype "passive"))
      (node (ref "L14") (pin "2") (pinfunction "2_2") (pintype "passive"))
      (node (ref "P6") (pin "2") (pinfunction "2_2") (pintype "passive"))
    )
    (net (code "42") (name "Net-(C43-Pad1)") (class "Default")
      (node (ref "C43") (pin "1") (pinfunction "1_1") (pintype "passive"))
      (node (ref "CLK1") (pin "1") (pintype "passive"))
      (node (ref "R11") (pin "2") (pinfunction "2_2") (pintype "passive"))
    )
    (net (code "43") (name "Net-(C43-Pad2)") (class "Default")
      (node (ref "C43") (pin "2") (pinfunction "2_2") (pintype "passive"))
      (node (ref "R1") (pin "1") (pinfunction "1_1") (pintype "passive"))
      (node (ref "R5") (pin "2") (pinfunction "2_2") (pintype "passive"))
      (node (ref "U5") (pin "2") (pinfunction "D_2") (pintype "passive"))
    )
    (net (code "44") (name "Net-(P4-Pad1)") (class "Default")
      (node (ref "P4") (pin "1") (pinfunction "1_1") (pintype "passive"))
      (node (ref "filtered I2") (pin "1") (pintype "passive"))
    )
    (net (code "45") (name "Net-(P6-Pad1)") (class "Default")
      (node (ref "P6") (pin "1") (pinfunction "1_1") (pintype "passive"))
      (node (ref "filtered I4") (pin "1") (pintype "passive"))
    )
    (net (code "46") (name "Net-(U1-EPAD)") (class "Default")
      (node (ref "C4") (pin "1") (pinfunction "1_1") (pintype "passive"))
      (node (ref "L1") (pin "1") (pinfunction "1_1") (pintype "passive"))
      (node (ref "U1") (pin "2") (pinfunction "OUTPUT_2") (pintype "output"))
      (node (ref "U1") (pin "4") (pinfunction "EPAD_4") (pintype "passive"))
    )
    (net (code "47") (name "Net-(U2-EPAD)") (class "Default")
      (node (ref "C8") (pin "1") (pinfunction "1_1") (pintype "passive"))
      (node (ref "L2") (pin "1") (pinfunction "1_1") (pintype "passive"))
      (node (ref "U2") (pin "2") (pinfunction "OUTPUT_2") (pintype "output"))
      (node (ref "U2") (pin "4") (pinfunction "EPAD_4") (pintype "passive"))
    )
    (net (code "48") (name "Net-(U3-DACBP)") (class "Default")
      (node (ref "C16") (pin "1") (pinfunction "1_1") (pintype "passive"))
      (node (ref "U3") (pin "55") (pinfunction "DACBP_55") (pintype "passive"))
    )
    (net (code "49") (name "Net-(U3-DACRSET)") (class "Default")
      (node (ref "R3") (pin "1") (pinfunction "1_1") (pintype "passive"))
      (node (ref "U3") (pin "56") (pinfunction "DACRSET_56") (pintype "passive"))
    )
    (net (code "50") (name "Net-(U3-IOUT1)") (class "Default")
      (node (ref "C20") (pin "1") (pinfunction "1_1") (pintype "passive"))
      (node (ref "C23") (pin "2") (pinfunction "2_2") (pintype "passive"))
      (node (ref "L7") (pin "1") (pinfunction "1_1") (pintype "passive"))
      (node (ref "R8") (pin "2") (pinfunction "2_2") (pintype "passive"))
      (node (ref "U3") (pin "48") (pinfunction "IOUT1_48") (pintype "passive"))
      (node (ref "unfiltered I1") (pin "1") (pintype "passive"))
    )
    (net (code "51") (name "Net-(U3-IOUT2)") (class "Default")
      (node (ref "C34") (pin "1") (pinfunction "1_1") (pintype "passive"))
      (node (ref "C37") (pin "2") (pinfunction "2_2") (pintype "passive"))
      (node (ref "L13") (pin "1") (pinfunction "1_1") (pintype "passive"))
      (node (ref "R10") (pin "2") (pinfunction "2_2") (pintype "passive"))
      (node (ref "U3") (pin "52") (pinfunction "IOUT2_52") (pintype "passive"))
      (node (ref "unfiltered I2") (pin "1") (pintype "passive"))
    )
    (net (code "52") (name "Net-(U3-PLLFILTER)") (class "Default")
      (node (ref "R4") (pin "1") (pinfunction "1_1") (pintype "passive"))
      (node (ref "U3") (pin "61") (pinfunction "PLLFILTER_61") (pintype "passive"))
    )
    (net (code "53") (name "Net-(U3-VOUT)") (class "Default")
      (node (ref "U3") (pin "36") (pinfunction "VOUT_36") (pintype "passive"))
      (node (ref "VOUT1") (pin "1") (pintype "passive"))
    )
    (net (code "54") (name "Net-(U3-~{IOUT1})") (class "Default")
      (node (ref "C12") (pin "2") (pinfunction "2_2") (pintype "passive"))
      (node (ref "C9") (pin "1") (pinfunction "1_1") (pintype "passive"))
      (node (ref "L3") (pin "1") (pinfunction "1_1") (pintype "passive"))
      (node (ref "R2") (pin "2") (pinfunction "2_2") (pintype "passive"))
      (node (ref "U3") (pin "49") (pinfunction "~{IOUT1}_49") (pintype "passive"))
    )
    (net (code "55") (name "Net-(U3-~{IOUT2})") (class "Default")
      (node (ref "C27") (pin "1") (pinfunction "1_1") (pintype "passive"))
      (node (ref "C30") (pin "2") (pinfunction "2_2") (pintype "passive"))
      (node (ref "L10") (pin "1") (pinfunction "1_1") (pintype "passive"))
      (node (ref "R9") (pin "2") (pinfunction "2_2") (pintype "passive"))
      (node (ref "U3") (pin "51") (pinfunction "~{IOUT2}_51") (pintype "passive"))
    )
    (net (code "56") (name "Net-(U4-OUT)") (class "Default")
      (node (ref "R5") (pin "1") (pinfunction "1_1") (pintype "passive"))
      (node (ref "U4") (pin "3") (pinfunction "OUT_3") (pintype "passive"))
    )
    (net (code "57") (name "Net-(U4-VDD)") (class "Default")
      (node (ref "C18") (pin "1") (pinfunction "1_1") (pintype "passive"))
      (node (ref "L6") (pin "1") (pinfunction "1_1") (pintype "passive"))
      (node (ref "U4") (pin "4") (pinfunction "VDD_4") (pintype "passive"))
    )
    (net (code "58") (name "Net-(U5-Vbb)") (class "Default")
      (node (ref "R1") (pin "2") (pinfunction "2_2") (pintype "passive"))
      (node (ref "U5") (pin "3") (pinfunction "D_3") (pintype "passive"))
      (node (ref "U5") (pin "4") (pinfunction "Vbb_4") (pintype "passive"))
    )
    (net (code "59") (name "Net-(U5-Vcc)") (class "Default")
      (node (ref "C41") (pin "2") (pinfunction "2_2") (pintype "passive"))
      (node (ref "L16") (pin "1") (pinfunction "1_1") (pintype "passive"))
      (node (ref "U5") (pin "8") (pinfunction "Vcc_8") (pintype "passive"))
    )
    (net (code "60") (name "VINN") (class "Default")
      (node (ref "P6") (pin "3") (pinfunction "3_3") (pintype "passive"))
      (node (ref "R6") (pin "2") (pinfunction "2_2") (pintype "passive"))
      (node (ref "U3") (pin "43") (pinfunction "VINN_43") (pintype "passive"))
    )
    (net (code "61") (name "VINP") (class "Default")
      (node (ref "P4") (pin "3") (pinfunction "3_3") (pintype "passive"))
      (node (ref "R7") (pin "2") (pinfunction "2_2") (pintype "passive"))
      (node (ref "U3") (pin "42") (pinfunction "VINP_42") (pintype "passive"))
    )
    (net (code "62") (name "unconnected-(P1-Pad11)") (class "Default")
      (node (ref "P1") (pin "11") (pinfunction "11_11") (pintype "passive"))
    )
    (net (code "63") (name "unconnected-(P2-Pad1)") (class "Default")
      (node (ref "P2") (pin "1") (pinfunction "1_1") (pintype "passive"))
    )
    (net (code "64") (name "unconnected-(P2-Pad2)") (class "Default")
      (node (ref "P2") (pin "2") (pinfunction "2_2") (pintype "passive"))
    )
    (net (code "65") (name "unconnected-(P2-Pad3)") (class "Default")
      (node (ref "P2") (pin "3") (pinfunction "3_3") (pintype "passive"))
    )
    (net (code "66") (name "unconnected-(P2-Pad4)") (class "Default")
      (node (ref "P2") (pin "4") (pinfunction "4_4") (pintype "passive"))
    )
    (net (code "67") (name "unconnected-(P2-Pad5)") (class "Default")
      (node (ref "P2") (pin "5") (pinfunction "5_5") (pintype "passive"))
    )
    (net (code "68") (name "unconnected-(P2-Pad6)") (class "Default")
      (node (ref "P2") (pin "6") (pinfunction "6_6") (pintype "passive"))
    )
    (net (code "69") (name "unconnected-(P2-Pad7)") (class "Default")
      (node (ref "P2") (pin "7") (pinfunction "7_7") (pintype "passive"))
    )
    (net (code "70") (name "unconnected-(P2-Pad8)") (class "Default")
      (node (ref "P2") (pin "8") (pinfunction "8_8") (pintype "passive"))
    )
    (net (code "71") (name "unconnected-(P2-Pad9)") (class "Default")
      (node (ref "P2") (pin "9") (pinfunction "9_9") (pintype "passive"))
    )
    (net (code "72") (name "unconnected-(P2-Pad10)") (class "Default")
      (node (ref "P2") (pin "10") (pinfunction "10_10") (pintype "passive"))
    )
    (net (code "73") (name "unconnected-(P2-Pad11)") (class "Default")
      (node (ref "P2") (pin "11") (pinfunction "11_11") (pintype "passive"))
    )
    (net (code "74") (name "unconnected-(P2-Pad12)") (class "Default")
      (node (ref "P2") (pin "12") (pinfunction "12_12") (pintype "passive"))
    )
    (net (code "75") (name "unconnected-(P2-Pad13)") (class "Default")
      (node (ref "P2") (pin "13") (pinfunction "13_13") (pintype "passive"))
    )
    (net (code "76") (name "unconnected-(P2-Pad14)") (class "Default")
      (node (ref "P2") (pin "14") (pinfunction "14_14") (pintype "passive"))
    )
    (net (code "77") (name "unconnected-(P2-Pad15)") (class "Default")
      (node (ref "P2") (pin "15") (pinfunction "15_15") (pintype "passive"))
    )
    (net (code "78") (name "unconnected-(P2-Pad16)") (class "Default")
      (node (ref "P2") (pin "16") (pinfunction "16_16") (pintype "passive"))
    )
    (net (code "79") (name "unconnected-(P2-Pad17)") (class "Default")
      (node (ref "P2") (pin "17") (pinfunction "17_17") (pintype "passive"))
    )
    (net (code "80") (name "unconnected-(P2-Pad18)") (class "Default")
      (node (ref "P2") (pin "18") (pinfunction "18_18") (pintype "passive"))
    )
    (net (code "81") (name "unconnected-(P2-Pad19)") (class "Default")
      (node (ref "P2") (pin "19") (pinfunction "19_19") (pintype "passive"))
    )
    (net (code "82") (name "unconnected-(P2-Pad20)") (class "Default")
      (node (ref "P2") (pin "20") (pinfunction "20_20") (pintype "passive"))
    )
    (net (code "83") (name "unconnected-(U3-NC-Pad13)") (class "Default")
      (node (ref "U3") (pin "13") (pinfunction "NC_13") (pintype "passive"))
    )
    (net (code "84") (name "unconnected-(U3-NC-Pad35)") (class "Default")
      (node (ref "U3") (pin "35") (pinfunction "NC_35") (pintype "passive"))
    )
    (net (code "85") (name "unconnected-(U3-NC-Pad57)") (class "Default")
      (node (ref "U3") (pin "57") (pinfunction "NC_57") (pintype "passive"))
    )
    (net (code "86") (name "unconnected-(U3-NC-Pad58)") (class "Default")
      (node (ref "U3") (pin "58") (pinfunction "NC_58") (pintype "passive"))
    )
    (net (code "87") (name "unconnected-(U3-NC-Pad63)") (class "Default")
      (node (ref "U3") (pin "63") (pinfunction "NC_63") (pintype "passive"))
    )
    (net (code "88") (name "unconnected-(U4-NC-Pad1)") (class "Default")
      (node (ref "U4") (pin "1") (pinfunction "NC_1") (pintype "passive"))
    )
    (net (code "89") (name "unconnected-(U5-NC-Pad1)") (class "Default")
      (node (ref "U5") (pin "1") (pinfunction "NC_1") (pintype "passive"))
    )
  )
)
